# 1-Schematic_Arduino_Uno.net
KiCad netlist of a schematic drawn in EasyEDA
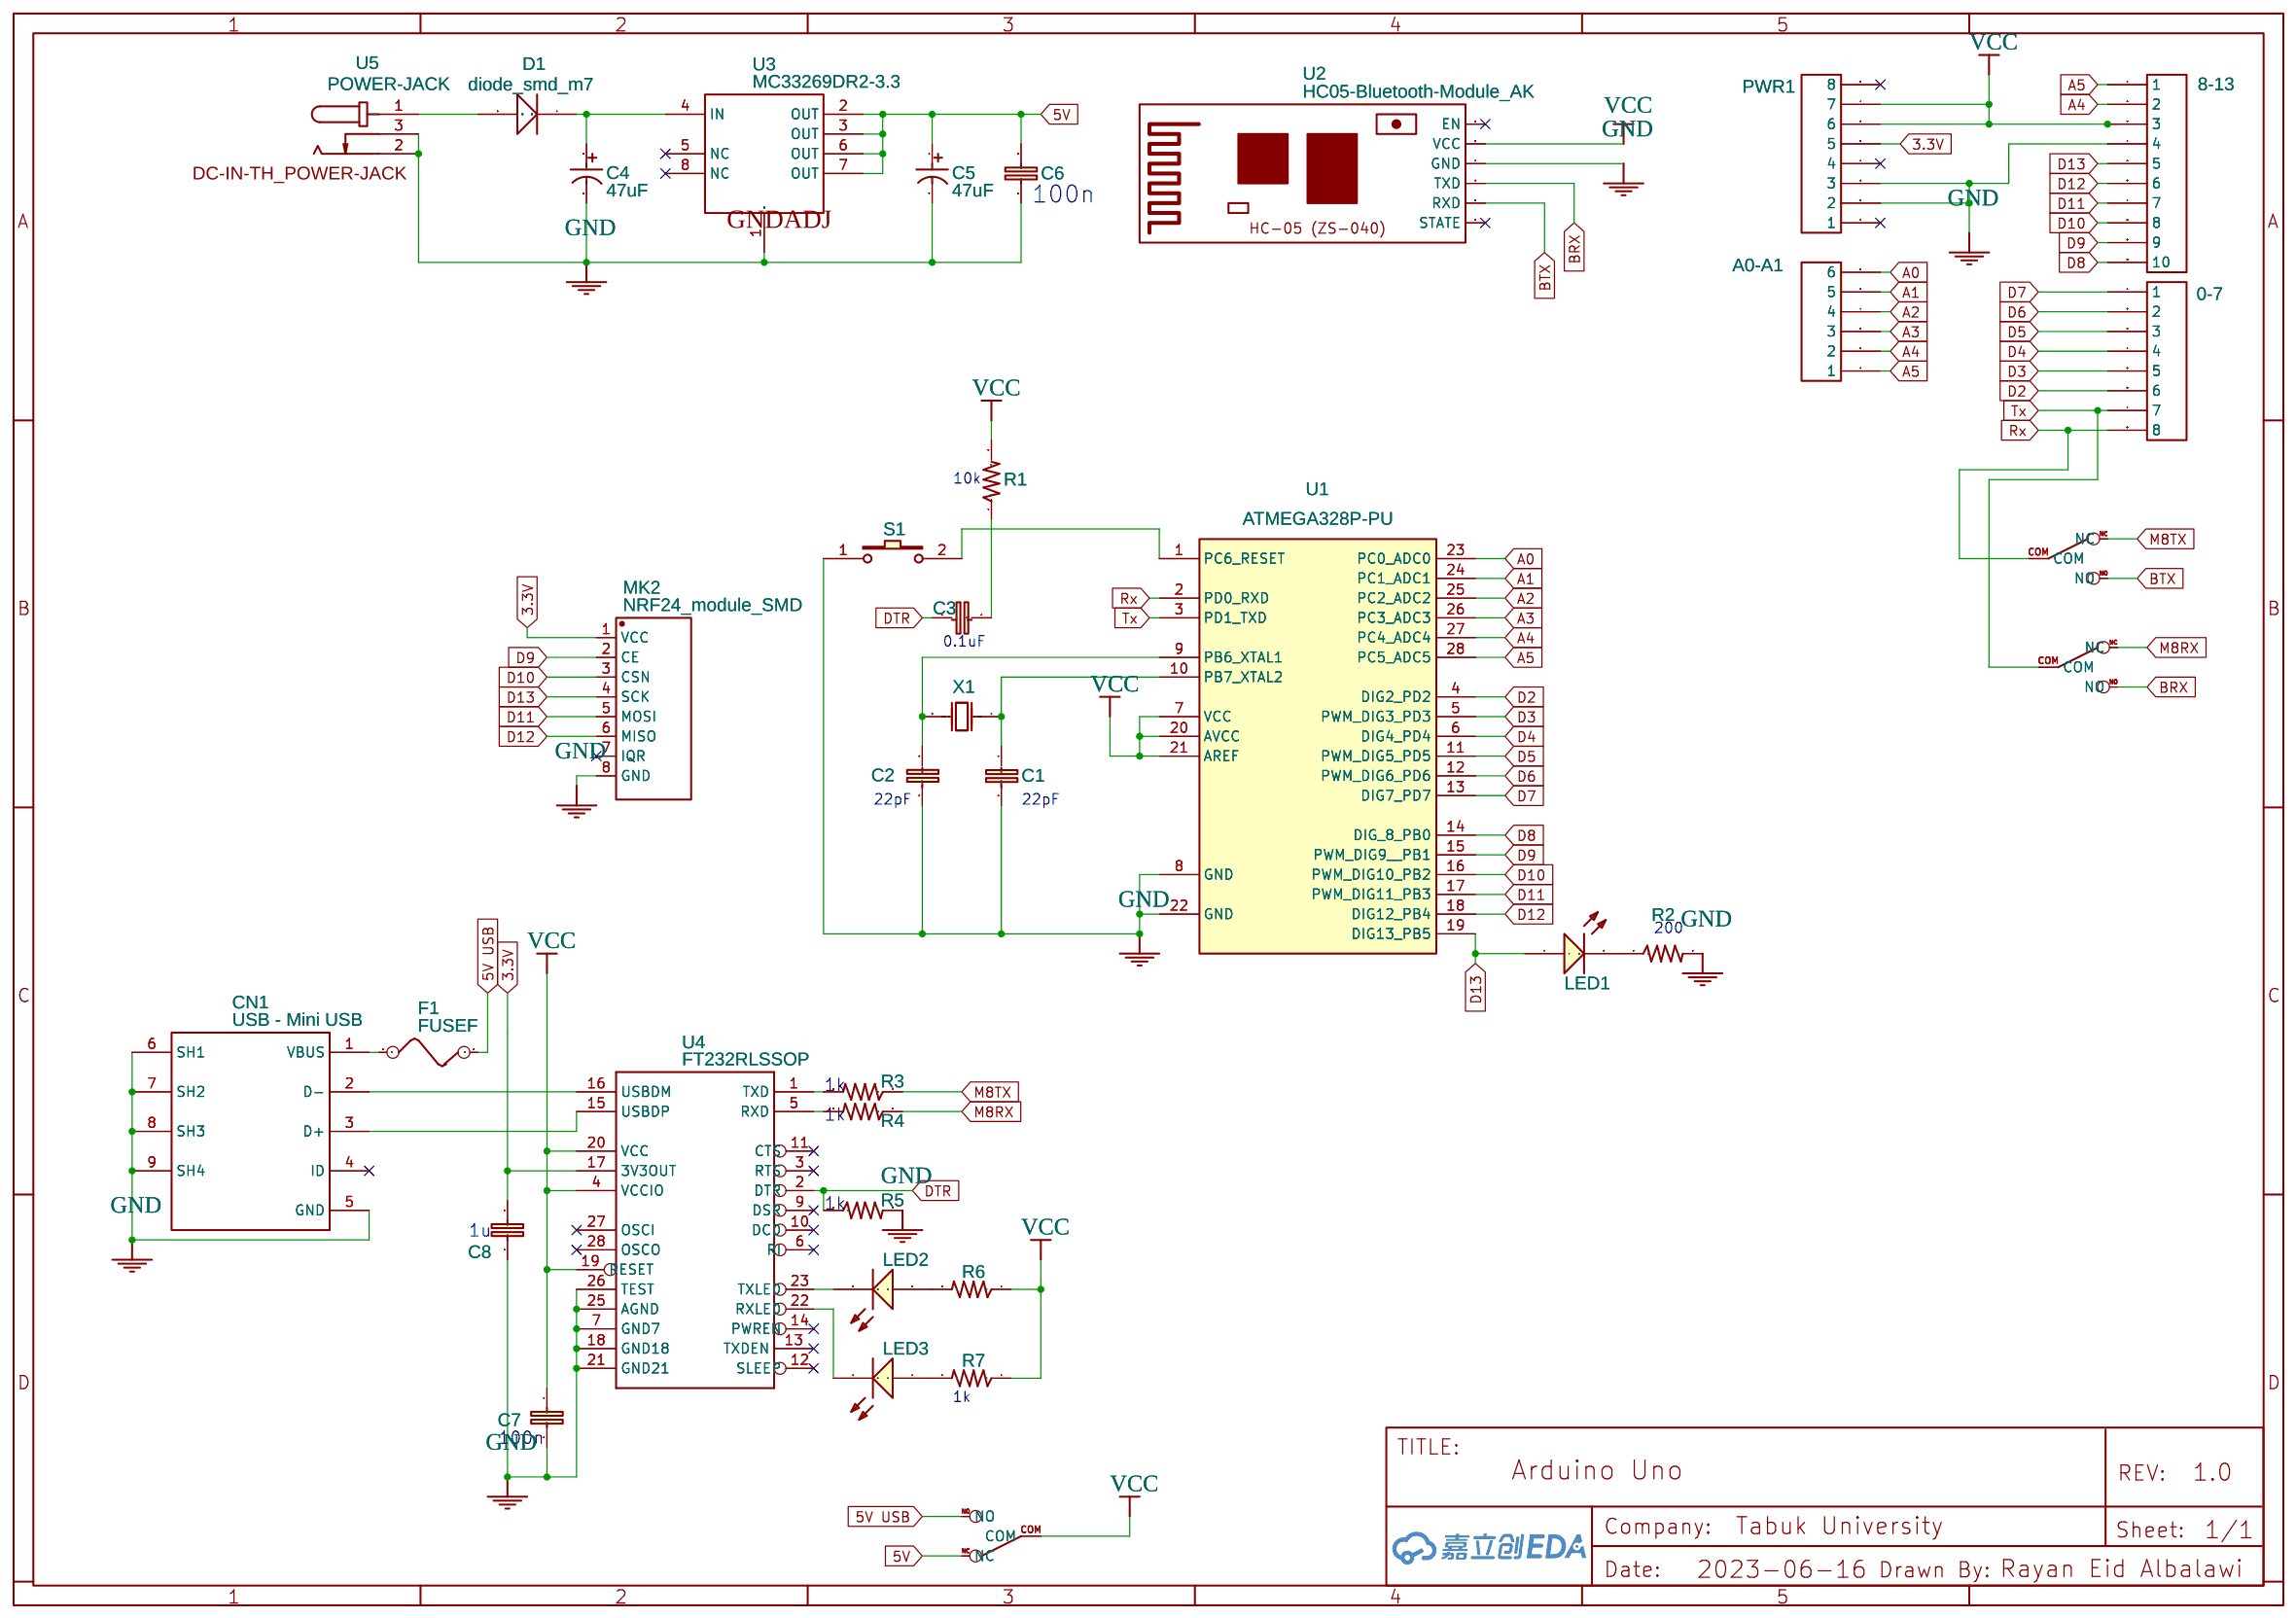
[diagram p0: schematic sheet]

(export (version "E")
  (design (tool "Eeschema 10.0.6"))
  (components
    (comp (ref "0-7")
      (value "0-7")
      (fields (field (name "Manufacturer Part") "Header2.54mm 1*8P") (field (name "Manufacturer") "ReliaPro"))
      (libsource (lib "") (part "Unknown_1070_-635"))
    )
    (comp (ref "8-13")
      (value "8-Aref")
      (fields
        (field (name "Manufacturer Part") "Headers  Pins2.54mm1*10P")
        (field (name "Manufacturer") "ReliaPro")
      )
      (libsource (lib "") (part "Unknown_1070_-730"))
    )
    (comp (ref "A0-A1")
      (value "Analogs")
      (fields
        (field (name "Manufacturer Part") "Header-Male-2.54_1x6")
        (field (name "Manufacturer") "BOOMELE")
      )
      (libsource (lib "") (part "Unknown_935_-645"))
    )
    (comp (ref "C1")
      (value "CAPACITOR_NPOL-0805")
      (fields (field (name "Manufacturer Part") "?"))
      (libsource (lib "") (part "Unknown_500_-415"))
    )
    (comp (ref "C2")
      (value "CAPACITOR_NPOL-0805")
      (fields (field (name "Manufacturer Part") "?"))
      (libsource (lib "") (part "Unknown_460_-425"))
    )
    (comp (ref "C3")
      (value "CAPACITOR_NPOL-0805")
      (fields (field (name "Manufacturer Part") "?"))
      (libsource (lib "") (part "Unknown_485_-500"))
    )
    (comp (ref "C4")
      (value "47uF")
      (fields (field (name "Manufacturer Part") "EEE-HD1C470AP") (field (name "Manufacturer") "Panasonic"))
      (libsource (lib "") (part "Unknown_290_-725"))
    )
    (comp (ref "C5")
      (value "47uF")
      (fields (field (name "Manufacturer Part") "EEE-HD1C470AP") (field (name "Manufacturer") "Panasonic"))
      (libsource (lib "") (part "Unknown_465_-725"))
    )
    (comp (ref "C6")
      (value "CAPACITOR_NPOL-0805")
      (fields (field (name "Manufacturer Part") "?"))
      (libsource (lib "") (part "Unknown_510_-720"))
    )
    (comp (ref "C7")
      (value "CAPACITOR_NPOL-0805")
      (fields (field (name "Manufacturer Part") "?"))
      (libsource (lib "") (part "Unknown_270_-90"))
    )
    (comp (ref "C8")
      (value "CAPACITOR_NPOL-0805")
      (fields (field (name "Manufacturer Part") "?"))
      (libsource (lib "") (part "Unknown_250_-185"))
    )
    (comp (ref "CN1") (value "USB - Mini USB") (libsource (lib "") (part "Unknown_120_-250")))
    (comp (ref "D1")
      (value "diode_smd_m7")
      (fields (field (name "Manufacturer Part") "?"))
      (libsource (lib "") (part "diode_smd_m7"))
    )
    (comp (ref "F1")
      (value "FUSEF")
      (fields (field (name "Manufacturer Part") "?"))
      (libsource (lib "") (part "Unknown_215_-280"))
    )
    (comp (ref "LED1")
      (value "17-21/GHC-YR1S2/3T")
      (fields (field (name "Manufacturer") "EVERLIGHT"))
      (libsource (lib "") (part "Unknown_785_-330"))
    )
    (comp (ref "LED2")
      (value "17-21/GHC-YR1S2/3T")
      (fields (field (name "Manufacturer") "EVERLIGHT"))
      (libsource (lib "") (part "Unknown_445_-160"))
    )
    (comp (ref "LED3")
      (value "17-21/GHC-YR1S2/3T")
      (fields (field (name "Manufacturer") "EVERLIGHT"))
      (libsource (lib "") (part "Unknown_445_-115"))
    )
    (comp (ref "MK2")
      (value "NRF24_module_SMD")
      (fields (field (name "Manufacturer Part") "AS01-ML01S") (field (name "Manufacturer") "Ashining"))
      (libsource (lib "") (part "Unknown_305_-480"))
    )
    (comp (ref "PWR1")
      (value "Powers")
      (fields (field (name "Manufacturer Part") "Header2.54mm 1*8P") (field (name "Manufacturer") "ReliaPro"))
      (libsource (lib "") (part "Unknown_935_-730"))
    )
    (comp (ref "R1")
      (value "0.22OHM-1_4W-1%(0805)")
      (fields (field (name "Manufacturer Part") "?"))
      (libsource (lib "") (part "Unknown_495_-570"))
    )
    (comp (ref "R2")
      (value "200")
      (fields (field (name "Manufacturer Part") "?"))
      (libsource (lib "") (part "Unknown_835_-330"))
    )
    (comp (ref "R3")
      (value "200")
      (fields (field (name "Manufacturer Part") "?"))
      (libsource (lib "") (part "Unknown_430_-260"))
    )
    (comp (ref "R4")
      (value "200")
      (fields (field (name "Manufacturer Part") "?"))
      (libsource (lib "") (part "Unknown_430_-250"))
    )
    (comp (ref "R5")
      (value "200")
      (fields (field (name "Manufacturer Part") "?"))
      (libsource (lib "") (part "Unknown_430_-200"))
    )
    (comp (ref "R6")
      (value "200")
      (fields (field (name "Manufacturer Part") "?"))
      (libsource (lib "") (part "Unknown_485_-160"))
    )
    (comp (ref "R7")
      (value "200")
      (fields (field (name "Manufacturer Part") "?"))
      (libsource (lib "") (part "Unknown_485_-115"))
    )
    (comp (ref "S1")
      (value "Button1")
      (fields (field (name "Manufacturer Part") "?"))
      (libsource (lib "") (part "Unknown_440_-530"))
    )
    (comp (ref "SW1")
      (value "SW-SLIDE")
      (fields (field (name "Manufacturer Part") "?"))
      (libsource (lib "") (part "Unknown_490_-35"))
    )
    (comp (ref "SW2")
      (value "SW-SLIDE")
      (fields (field (name "Manufacturer Part") "?"))
      (libsource (lib "") (part "Unknown_1050_-530"))
    )
    (comp (ref "SW3")
      (value "SW-SLIDE")
      (fields (field (name "Manufacturer Part") "?"))
      (libsource (lib "") (part "Unknown_1055_-475"))
    )
    (comp (ref "U1")
      (value "ATMEGA328P-PU")
      (fields (field (name "Manufacturer") "ATMEL"))
      (libsource (lib "") (part "Unknown_640_-410"))
    )
    (comp (ref "U2")
      (value "HC05-Bluetooth-Module_AK")
      (libsource (lib "") (part "HC05-Bluetooth-Module_AK"))
    )
    (comp (ref "U3")
      (value "MC33269DR2-3.3")
      (fields (field (name "Manufacturer") "ON"))
      (libsource (lib "") (part "Unknown_380_-725"))
    )
    (comp (ref "U4")
      (value "FT232RLSSOP")
      (fields (field (name "Manufacturer Part") "?"))
      (libsource (lib "") (part "Unknown_345_-190"))
    )
    (comp (ref "U5") (value "POWER-JACK") (libsource (lib "") (part "POWER-JACK")))
    (comp (ref "X1")
      (value "16MHZ")
      (fields (field (name "Manufacturer Part") "X49SD16MSD2SC") (field (name "Manufacturer") "YXC"))
      (libsource (lib "") (part "Unknown_480_-450"))
    )
  )
  (nets
    (net (code "1") (name "3.3V") (class "Default")
      (node (ref "C8") (pin "1") (pinfunction "1_1") (pintype "unspecified"))
      (node (ref "MK2") (pin "1") (pinfunction "VCC_1") (pintype "unspecified"))
      (node (ref "PWR1") (pin "5") (pinfunction "5_5") (pintype "input"))
      (node (ref "U4") (pin "17") (pinfunction "3V3OUT_17") (pintype "output"))
    )
    (net (code "2") (name "5V") (class "Default")
      (node (ref "C5") (pin "1") (pinfunction "1_1") (pintype "input"))
      (node (ref "C6") (pin "1") (pinfunction "1_1") (pintype "unspecified"))
      (node (ref "SW1") (pin "NC") (pinfunction "NC_NC") (pintype "unspecified"))
      (node (ref "U3") (pin "2") (pinfunction "OUT_2") (pintype "passive"))
      (node (ref "U3") (pin "3") (pinfunction "OUT_3") (pintype "passive"))
      (node (ref "U3") (pin "6") (pinfunction "OUT_6") (pintype "passive"))
      (node (ref "U3") (pin "7") (pinfunction "OUT_7") (pintype "passive"))
    )
    (net (code "3") (name "5V USB") (class "Default")
      (node (ref "F1") (pin "2") (pinfunction "2_2") (pintype "unspecified"))
      (node (ref "SW1") (pin "NO") (pinfunction "NO_NO") (pintype "unspecified"))
    )
    (net (code "4") (name "A0") (class "Default")
      (node (ref "A0-A1") (pin "6") (pinfunction "6_6") (pintype "input"))
      (node (ref "U1") (pin "23") (pinfunction "PC0_ADC0_23") (pintype "bidirectional"))
    )
    (net (code "5") (name "A1") (class "Default")
      (node (ref "A0-A1") (pin "5") (pinfunction "5_5") (pintype "input"))
      (node (ref "U1") (pin "24") (pinfunction "PC1_ADC1_24") (pintype "bidirectional"))
    )
    (net (code "6") (name "A2") (class "Default")
      (node (ref "A0-A1") (pin "4") (pinfunction "4_4") (pintype "input"))
      (node (ref "U1") (pin "25") (pinfunction "PC2_ADC2_25") (pintype "bidirectional"))
    )
    (net (code "7") (name "A3") (class "Default")
      (node (ref "A0-A1") (pin "3") (pinfunction "3_3") (pintype "input"))
      (node (ref "U1") (pin "26") (pinfunction "PC3_ADC3_26") (pintype "bidirectional"))
    )
    (net (code "8") (name "A4") (class "Default")
      (node (ref "8-13") (pin "2") (pinfunction "2_2") (pintype "input"))
      (node (ref "A0-A1") (pin "2") (pinfunction "2_2") (pintype "input"))
      (node (ref "U1") (pin "27") (pinfunction "PC4_ADC4_27") (pintype "bidirectional"))
    )
    (net (code "9") (name "A5") (class "Default")
      (node (ref "8-13") (pin "1") (pinfunction "1_1") (pintype "input"))
      (node (ref "A0-A1") (pin "1") (pinfunction "1_1") (pintype "input"))
      (node (ref "U1") (pin "28") (pinfunction "PC5_ADC5_28") (pintype "bidirectional"))
    )
    (net (code "10") (name "BRX") (class "Default")
      (node (ref "SW3") (pin "NO") (pinfunction "NO_NO") (pintype "unspecified"))
      (node (ref "U2") (pin "3") (pinfunction "TXD_3") (pintype "passive"))
    )
    (net (code "11") (name "BTX") (class "Default")
      (node (ref "SW2") (pin "NO") (pinfunction "NO_NO") (pintype "unspecified"))
      (node (ref "U2") (pin "2") (pinfunction "RXD_2") (pintype "passive"))
    )
    (net (code "12") (name "D2") (class "Default")
      (node (ref "0-7") (pin "6") (pinfunction "6_6") (pintype "input"))
      (node (ref "U1") (pin "4") (pinfunction "DIG2_PD2_4") (pintype "bidirectional"))
    )
    (net (code "13") (name "D3") (class "Default")
      (node (ref "0-7") (pin "5") (pinfunction "5_5") (pintype "input"))
      (node (ref "U1") (pin "5") (pinfunction "PWM_DIG3_PD3_5") (pintype "bidirectional"))
    )
    (net (code "14") (name "D4") (class "Default")
      (node (ref "0-7") (pin "4") (pinfunction "4_4") (pintype "input"))
      (node (ref "U1") (pin "6") (pinfunction "DIG4_PD4_6") (pintype "bidirectional"))
    )
    (net (code "15") (name "D5") (class "Default")
      (node (ref "0-7") (pin "3") (pinfunction "3_3") (pintype "input"))
      (node (ref "U1") (pin "11") (pinfunction "PWM_DIG5_PD5_11") (pintype "bidirectional"))
    )
    (net (code "16") (name "D6") (class "Default")
      (node (ref "0-7") (pin "2") (pinfunction "2_2") (pintype "input"))
      (node (ref "U1") (pin "12") (pinfunction "PWM_DIG6_PD6_12") (pintype "bidirectional"))
    )
    (net (code "17") (name "D7") (class "Default")
      (node (ref "0-7") (pin "1") (pinfunction "1_1") (pintype "input"))
      (node (ref "U1") (pin "13") (pinfunction "DIG7_PD7_13") (pintype "bidirectional"))
    )
    (net (code "18") (name "D8") (class "Default")
      (node (ref "8-13") (pin "10") (pinfunction "10_10") (pintype "input"))
      (node (ref "U1") (pin "14") (pinfunction "DIG_8_PB0_14") (pintype "bidirectional"))
    )
    (net (code "19") (name "D9") (class "Default")
      (node (ref "8-13") (pin "9") (pinfunction "9_9") (pintype "input"))
      (node (ref "MK2") (pin "2") (pinfunction "CE_2") (pintype "unspecified"))
      (node (ref "U1") (pin "15") (pinfunction "PWM_DIG9__PB1_15") (pintype "bidirectional"))
    )
    (net (code "20") (name "D10") (class "Default")
      (node (ref "8-13") (pin "8") (pinfunction "8_8") (pintype "input"))
      (node (ref "MK2") (pin "3") (pinfunction "CSN_3") (pintype "unspecified"))
      (node (ref "U1") (pin "16") (pinfunction "PWM_DIG10_PB2_16") (pintype "bidirectional"))
    )
    (net (code "21") (name "D11") (class "Default")
      (node (ref "8-13") (pin "7") (pinfunction "7_7") (pintype "input"))
      (node (ref "MK2") (pin "5") (pinfunction "MOSI_5") (pintype "unspecified"))
      (node (ref "U1") (pin "17") (pinfunction "PWM_DIG11_PB3_17") (pintype "bidirectional"))
    )
    (net (code "22") (name "D12") (class "Default")
      (node (ref "8-13") (pin "6") (pinfunction "6_6") (pintype "input"))
      (node (ref "MK2") (pin "6") (pinfunction "MISO_6") (pintype "unspecified"))
      (node (ref "U1") (pin "18") (pinfunction "DIG12_PB4_18") (pintype "bidirectional"))
    )
    (net (code "23") (name "D13") (class "Default")
      (node (ref "8-13") (pin "5") (pinfunction "5_5") (pintype "input"))
      (node (ref "LED1") (pin "1") (pinfunction "A_1") (pintype "input"))
      (node (ref "MK2") (pin "4") (pinfunction "SCK_4") (pintype "unspecified"))
      (node (ref "U1") (pin "19") (pinfunction "DIG13_PB5_19") (pintype "bidirectional"))
    )
    (net (code "24") (name "DTR") (class "Default")
      (node (ref "C3") (pin "1") (pinfunction "1_1") (pintype "unspecified"))
      (node (ref "R5") (pin "1") (pinfunction "1_1") (pintype "unspecified"))
      (node (ref "U4") (pin "2") (pinfunction "DTR_2") (pintype "output"))
    )
    (net (code "25") (name "GND") (class "Default")
      (node (ref "8-13") (pin "4") (pinfunction "4_4") (pintype "input"))
      (node (ref "C1") (pin "2") (pinfunction "2_2") (pintype "unspecified"))
      (node (ref "C2") (pin "1") (pinfunction "1_1") (pintype "unspecified"))
      (node (ref "C4") (pin "2") (pinfunction "2_2") (pintype "input"))
      (node (ref "C5") (pin "2") (pinfunction "2_2") (pintype "input"))
      (node (ref "C6") (pin "2") (pinfunction "2_2") (pintype "unspecified"))
      (node (ref "C7") (pin "2") (pinfunction "2_2") (pintype "unspecified"))
      (node (ref "C8") (pin "2") (pinfunction "2_2") (pintype "unspecified"))
      (node (ref "CN1") (pin "5") (pinfunction "GND_5") (pintype "passive"))
      (node (ref "CN1") (pin "6") (pinfunction "SH1_6") (pintype "passive"))
      (node (ref "CN1") (pin "7") (pinfunction "SH2_7") (pintype "passive"))
      (node (ref "CN1") (pin "8") (pinfunction "SH3_8") (pintype "passive"))
      (node (ref "CN1") (pin "9") (pinfunction "SH4_9") (pintype "passive"))
      (node (ref "MK2") (pin "8") (pinfunction "GND_8") (pintype "unspecified"))
      (node (ref "PWR1") (pin "2") (pinfunction "2_2") (pintype "input"))
      (node (ref "PWR1") (pin "3") (pinfunction "3_3") (pintype "input"))
      (node (ref "R2") (pin "2") (pinfunction "2_2") (pintype "unspecified"))
      (node (ref "R5") (pin "2") (pinfunction "2_2") (pintype "unspecified"))
      (node (ref "S1") (pin "1") (pintype "unspecified"))
      (node (ref "U1") (pin "22") (pinfunction "GND_22") (pintype "passive"))
      (node (ref "U1") (pin "8") (pinfunction "GND_8") (pintype "passive"))
      (node (ref "U2") (pin "4") (pinfunction "GND_4") (pintype "input"))
      (node (ref "U3") (pin "1") (pinfunction "GNDADJ_1") (pintype "passive"))
      (node (ref "U4") (pin "18") (pinfunction "GND18_18") (pintype "passive"))
      (node (ref "U4") (pin "21") (pinfunction "GND21_21") (pintype "passive"))
      (node (ref "U4") (pin "25") (pinfunction "AGND_25") (pintype "passive"))
      (node (ref "U4") (pin "26") (pinfunction "TEST_26") (pintype "input"))
      (node (ref "U4") (pin "7") (pinfunction "GND7_7") (pintype "passive"))
      (node (ref "U5") (pin "2") (pinfunction "2_2") (pintype "unspecified"))
      (node (ref "U5") (pin "3") (pinfunction "3_3") (pintype "unspecified"))
    )
    (net (code "26") (name "M8RX") (class "Default")
      (node (ref "R4") (pin "1") (pinfunction "1_1") (pintype "unspecified"))
      (node (ref "SW3") (pin "NC") (pinfunction "NC_NC") (pintype "unspecified"))
    )
    (net (code "27") (name "M8TX") (class "Default")
      (node (ref "R3") (pin "1") (pinfunction "1_1") (pintype "unspecified"))
      (node (ref "SW2") (pin "NC") (pinfunction "NC_NC") (pintype "unspecified"))
    )
    (net (code "28") (name "Net-(C3-Pad2)") (class "Default")
      (node (ref "C3") (pin "2") (pinfunction "2_2") (pintype "unspecified"))
      (node (ref "R1") (pin "1") (pinfunction "1_1") (pintype "unspecified"))
    )
    (net (code "29") (name "Net-(CN1-D+)") (class "Default")
      (node (ref "CN1") (pin "3") (pinfunction "D+_3") (pintype "bidirectional"))
      (node (ref "U4") (pin "15") (pinfunction "USBDP_15") (pintype "unspecified"))
    )
    (net (code "30") (name "Net-(CN1-D-)") (class "Default")
      (node (ref "CN1") (pin "2") (pinfunction "D-_2") (pintype "bidirectional"))
      (node (ref "U4") (pin "16") (pinfunction "USBDM_16") (pintype "unspecified"))
    )
    (net (code "31") (name "Net-(CN1-VBUS)") (class "Default")
      (node (ref "CN1") (pin "1") (pinfunction "VBUS_1") (pintype "passive"))
      (node (ref "F1") (pin "1") (pinfunction "1_1") (pintype "unspecified"))
    )
    (net (code "32") (name "Net-(D1-анод)") (class "Default")
      (node (ref "D1") (pin "2") (pinfunction "анод_2") (pintype "unspecified"))
      (node (ref "U5") (pin "1") (pinfunction "1_1") (pintype "unspecified"))
    )
    (net (code "33") (name "Net-(D1-катод)") (class "Default")
      (node (ref "C4") (pin "1") (pinfunction "1_1") (pintype "input"))
      (node (ref "D1") (pin "1") (pinfunction "катод_1") (pintype "unspecified"))
      (node (ref "U3") (pin "4") (pinfunction "IN_4") (pintype "passive"))
    )
    (net (code "34") (name "Net-(LED1-C)") (class "Default")
      (node (ref "LED1") (pin "2") (pinfunction "C_2") (pintype "input"))
      (node (ref "R2") (pin "1") (pinfunction "1_1") (pintype "unspecified"))
    )
    (net (code "35") (name "Net-(LED2-A)") (class "Default")
      (node (ref "LED2") (pin "1") (pinfunction "A_1") (pintype "input"))
      (node (ref "R6") (pin "2") (pinfunction "2_2") (pintype "unspecified"))
    )
    (net (code "36") (name "Net-(LED2-C)") (class "Default")
      (node (ref "LED2") (pin "2") (pinfunction "C_2") (pintype "input"))
      (node (ref "U4") (pin "23") (pinfunction "TXLED_23") (pintype "input"))
    )
    (net (code "37") (name "Net-(LED3-A)") (class "Default")
      (node (ref "LED3") (pin "1") (pinfunction "A_1") (pintype "input"))
      (node (ref "R7") (pin "2") (pinfunction "2_2") (pintype "unspecified"))
    )
    (net (code "38") (name "Net-(LED3-C)") (class "Default")
      (node (ref "LED3") (pin "2") (pinfunction "C_2") (pintype "input"))
      (node (ref "U4") (pin "22") (pinfunction "RXLED_22") (pintype "input"))
    )
    (net (code "39") (name "Net-(U1-PB6_XTAL1)") (class "Default")
      (node (ref "C2") (pin "2") (pinfunction "2_2") (pintype "unspecified"))
      (node (ref "U1") (pin "9") (pinfunction "PB6_XTAL1_9") (pintype "bidirectional"))
      (node (ref "X1") (pin "2") (pinfunction "OSC2_2") (pintype "input"))
    )
    (net (code "40") (name "Net-(U1-PB7_XTAL2)") (class "Default")
      (node (ref "C1") (pin "1") (pinfunction "1_1") (pintype "unspecified"))
      (node (ref "U1") (pin "10") (pinfunction "PB7_XTAL2_10") (pintype "bidirectional"))
      (node (ref "X1") (pin "1") (pinfunction "OSC1_1") (pintype "input"))
    )
    (net (code "41") (name "Net-(U1-PC6_RESET)") (class "Default")
      (node (ref "S1") (pin "2") (pintype "unspecified"))
      (node (ref "U1") (pin "1") (pinfunction "PC6_RESET_1") (pintype "bidirectional"))
    )
    (net (code "42") (name "Net-(U4-RXD)") (class "Default")
      (node (ref "R4") (pin "2") (pinfunction "2_2") (pintype "unspecified"))
      (node (ref "U4") (pin "5") (pinfunction "RXD_5") (pintype "input"))
    )
    (net (code "43") (name "Net-(U4-TXD)") (class "Default")
      (node (ref "R3") (pin "2") (pinfunction "2_2") (pintype "unspecified"))
      (node (ref "U4") (pin "1") (pinfunction "TXD_1") (pintype "output"))
    )
    (net (code "44") (name "Rx") (class "Default")
      (node (ref "0-7") (pin "8") (pinfunction "8_8") (pintype "input"))
      (node (ref "SW2") (pin "COM") (pinfunction "COM_COM") (pintype "unspecified"))
      (node (ref "U1") (pin "2") (pinfunction "PD0_RXD_2") (pintype "bidirectional"))
    )
    (net (code "45") (name "Tx") (class "Default")
      (node (ref "0-7") (pin "7") (pinfunction "7_7") (pintype "input"))
      (node (ref "SW3") (pin "COM") (pinfunction "COM_COM") (pintype "unspecified"))
      (node (ref "U1") (pin "3") (pinfunction "PD1_TXD_3") (pintype "bidirectional"))
    )
    (net (code "46") (name "VCC") (class "Default")
      (node (ref "8-13") (pin "3") (pinfunction "3_3") (pintype "input"))
      (node (ref "C7") (pin "1") (pinfunction "1_1") (pintype "unspecified"))
      (node (ref "PWR1") (pin "6") (pinfunction "6_6") (pintype "input"))
      (node (ref "PWR1") (pin "7") (pinfunction "7_7") (pintype "input"))
      (node (ref "R1") (pin "2") (pinfunction "2_2") (pintype "unspecified"))
      (node (ref "R6") (pin "1") (pinfunction "1_1") (pintype "unspecified"))
      (node (ref "R7") (pin "1") (pinfunction "1_1") (pintype "unspecified"))
      (node (ref "SW1") (pin "COM") (pinfunction "COM_COM") (pintype "unspecified"))
      (node (ref "U1") (pin "20") (pinfunction "AVCC_20") (pintype "passive"))
      (node (ref "U1") (pin "21") (pinfunction "AREF_21") (pintype "passive"))
      (node (ref "U1") (pin "7") (pinfunction "VCC_7") (pintype "passive"))
      (node (ref "U2") (pin "5") (pinfunction "VCC_5") (pintype "output"))
      (node (ref "U4") (pin "19") (pinfunction "RESET_19") (pintype "input"))
      (node (ref "U4") (pin "20") (pinfunction "VCC_20") (pintype "passive"))
      (node (ref "U4") (pin "4") (pinfunction "VCCIO_4") (pintype "passive"))
    )
    (net (code "47") (name "unconnected-(CN1-ID-Pad4)") (class "Default")
      (node (ref "CN1") (pin "4") (pinfunction "ID_4") (pintype "bidirectional+no_connect"))
    )
    (net (code "48") (name "unconnected-(MK2-IQR-Pad7)") (class "Default")
      (node (ref "MK2") (pin "7") (pinfunction "IQR_7") (pintype "unspecified+no_connect"))
    )
    (net (code "49") (name "unconnected-(PWR1-Pad1)") (class "Default")
      (node (ref "PWR1") (pin "1") (pinfunction "1_1") (pintype "input+no_connect"))
    )
    (net (code "50") (name "unconnected-(PWR1-Pad4)") (class "Default")
      (node (ref "PWR1") (pin "4") (pinfunction "4_4") (pintype "input+no_connect"))
    )
    (net (code "51") (name "unconnected-(PWR1-Pad8)") (class "Default")
      (node (ref "PWR1") (pin "8") (pinfunction "8_8") (pintype "input+no_connect"))
    )
    (net (code "52") (name "unconnected-(U2-EN-Pad6)") (class "Default")
      (node (ref "U2") (pin "6") (pinfunction "EN_6") (pintype "bidirectional+no_connect"))
    )
    (net (code "53") (name "unconnected-(U2-STATE-Pad1)") (class "Default")
      (node (ref "U2") (pin "1") (pinfunction "STATE_1") (pintype "passive+no_connect"))
    )
    (net (code "54") (name "unconnected-(U3-NC-Pad5)") (class "Default")
      (node (ref "U3") (pin "5") (pinfunction "NC_5") (pintype "unspecified+no_connect"))
    )
    (net (code "55") (name "unconnected-(U3-NC-Pad8)") (class "Default")
      (node (ref "U3") (pin "8") (pinfunction "NC_8") (pintype "unspecified+no_connect"))
    )
    (net (code "56") (name "unconnected-(U4-CTS-Pad11)") (class "Default")
      (node (ref "U4") (pin "11") (pinfunction "CTS_11") (pintype "input+no_connect"))
    )
    (net (code "57") (name "unconnected-(U4-DCD-Pad10)") (class "Default")
      (node (ref "U4") (pin "10") (pinfunction "DCD_10") (pintype "input+no_connect"))
    )
    (net (code "58") (name "unconnected-(U4-DSR-Pad9)") (class "Default")
      (node (ref "U4") (pin "9") (pinfunction "DSR_9") (pintype "input+no_connect"))
    )
    (net (code "59") (name "unconnected-(U4-OSCI-Pad27)") (class "Default")
      (node (ref "U4") (pin "27") (pinfunction "OSCI_27") (pintype "input+no_connect"))
    )
    (net (code "60") (name "unconnected-(U4-OSCO-Pad28)") (class "Default")
      (node (ref "U4") (pin "28") (pinfunction "OSCO_28") (pintype "output+no_connect"))
    )
    (net (code "61") (name "unconnected-(U4-PWREN-Pad14)") (class "Default")
      (node (ref "U4") (pin "14") (pinfunction "PWREN_14") (pintype "input+no_connect"))
    )
    (net (code "62") (name "unconnected-(U4-RI-Pad6)") (class "Default")
      (node (ref "U4") (pin "6") (pinfunction "RI_6") (pintype "input+no_connect"))
    )
    (net (code "63") (name "unconnected-(U4-RTS-Pad3)") (class "Default")
      (node (ref "U4") (pin "3") (pinfunction "RTS_3") (pintype "output+no_connect"))
    )
    (net (code "64") (name "unconnected-(U4-SLEEP-Pad12)") (class "Default")
      (node (ref "U4") (pin "12") (pinfunction "SLEEP_12") (pintype "input+no_connect"))
    )
    (net (code "65") (name "unconnected-(U4-TXDEN-Pad13)") (class "Default")
      (node (ref "U4") (pin "13") (pinfunction "TXDEN_13") (pintype "input+no_connect"))
    )
  )
)
